# ProPrj_PowMr-Hybrid-Inverter_2024-11-03.net
KiCad netlist of a schematic drawn in EasyEDA Pro
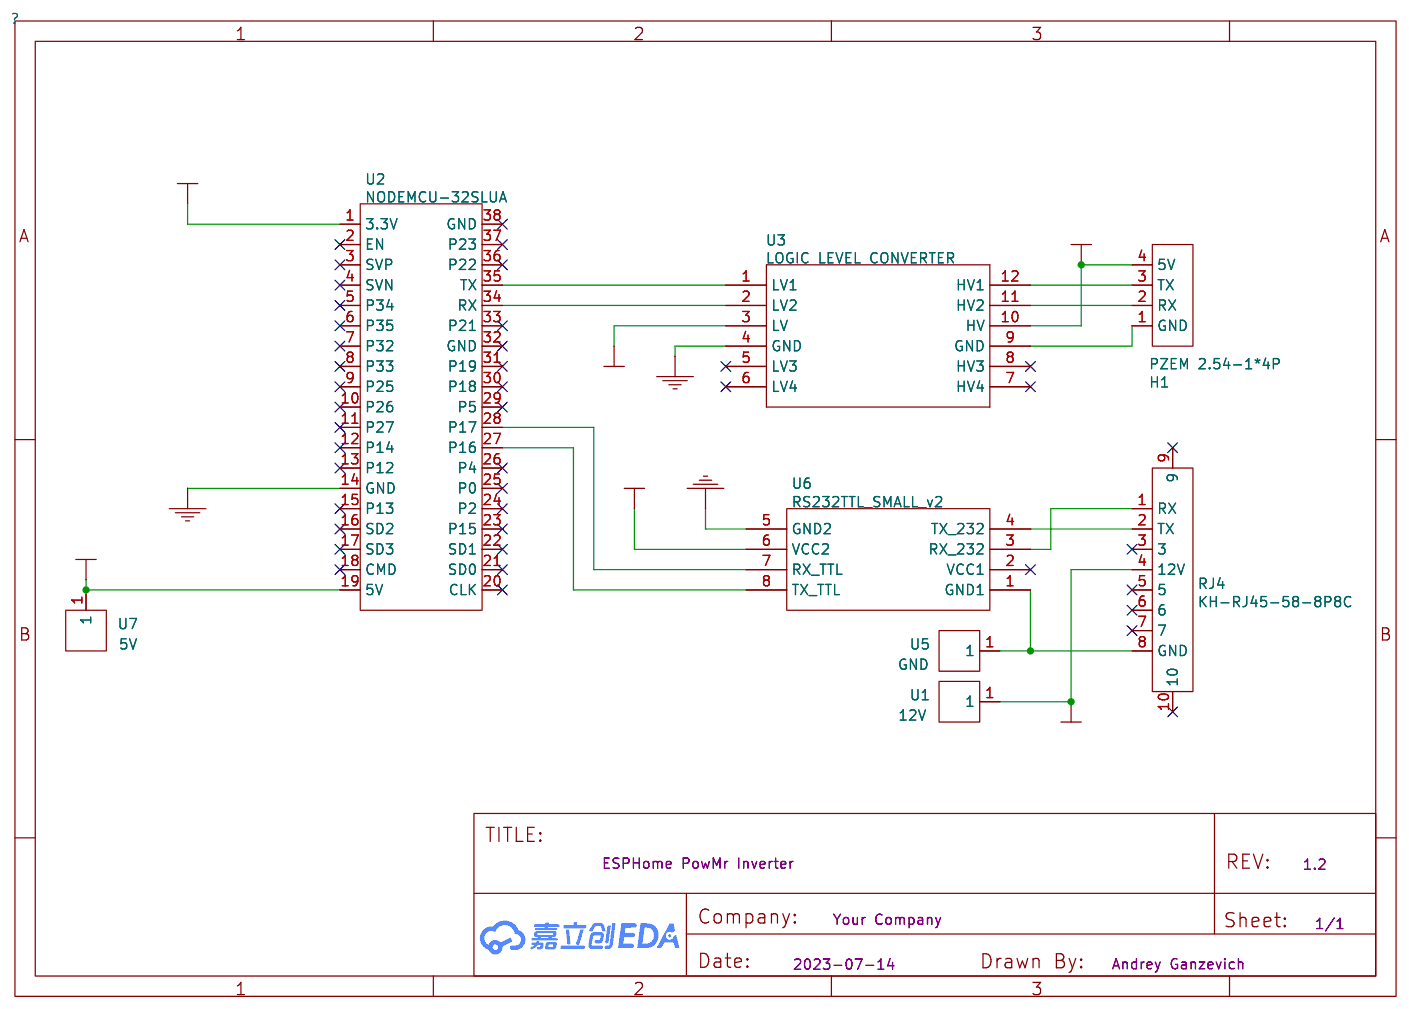
[diagram p0: Main board]
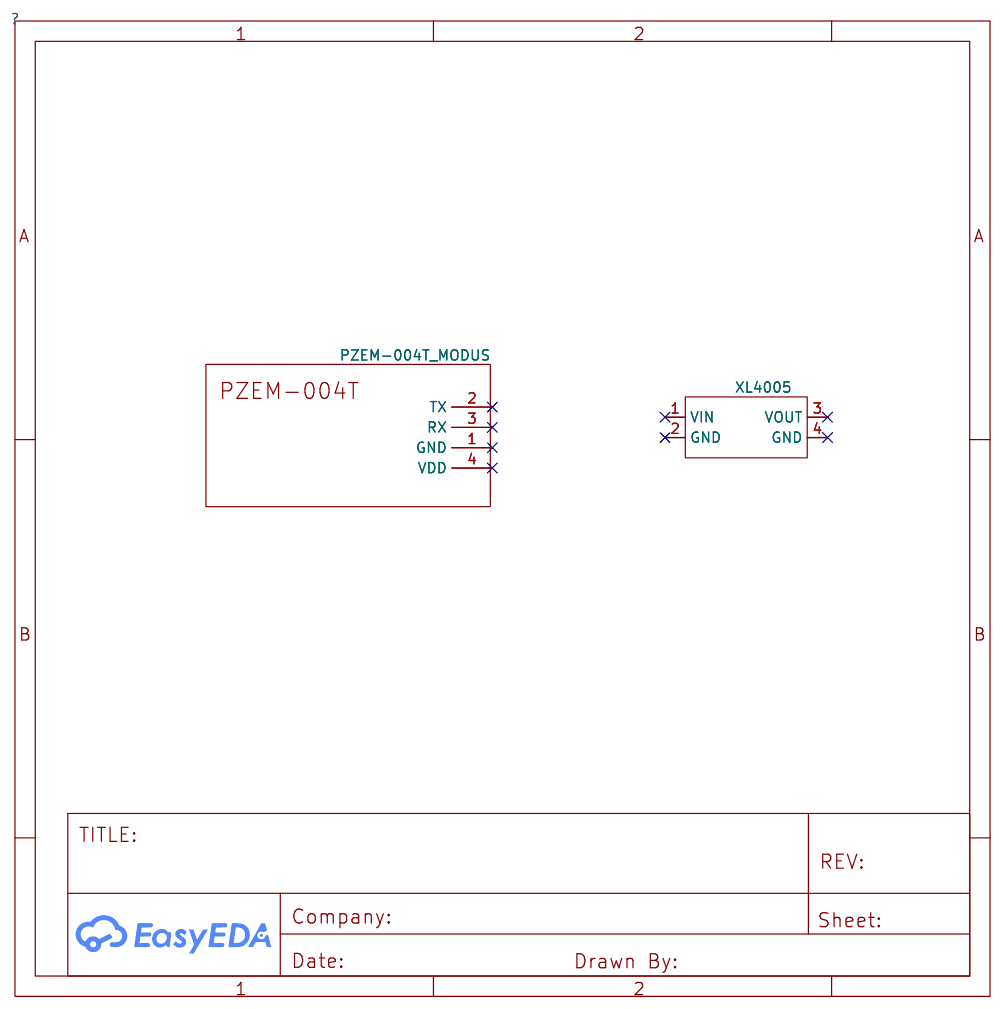
[diagram p1: Modules]

(export (version "E")
  (design (tool "Eeschema 10.0.6"))
  (components
    (comp (ref "H1")
      (value "PZEM 2.54-1*4P")
      (footprint "easyedapro:HDR-TH_4P-P2.54-H-M-W10.4")
      (fields
        (field (name "Manufacturer Part") "2.54-1*4P反弯排针")
        (field (name "Manufacturer") "BOOMELE(博穆精密)")
      )
      (libsource (lib "easyedapro") (part "PZEM 2.54-1*4P"))
    )
    (comp (ref "RJ4")
      (value "KH-RJ45-58-8P8C")
      (footprint "easyedapro:RJ45-TH_KH-RJ45-58-8P8C")
      (fields (field (name "Manufacturer") "kinghelm(金航标)"))
      (libsource (lib "easyedapro") (part "KH-RJ45-58-8P8C"))
    )
    (comp (ref "U1")
      (value "12V")
      (footprint "easyedapro:2X2MMPAD")
      (libsource (lib "easyedapro") (part "12V"))
    )
    (comp (ref "U2")
      (value "NODEMCU-32SLUA")
      (footprint "easyedapro:COMM-TH_NODEMCU-32SLUA")
      (fields
        (field (name "Manufacturer Part") "NodeMCU-32SLua")
        (field (name "Manufacturer") "Ai-Thinker(安信可)")
      )
      (libsource (lib "easyedapro") (part "NODEMCU-32SLUA"))
    )
    (comp (ref "U3")
      (value "LOGIC LEVEL CONVERTER")
      (footprint "easyedapro:LOGIC LEVEL CONVERTER")
      (libsource (lib "easyedapro") (part "LOGIC LEVEL CONVERTER"))
    )
    (comp (ref "U5")
      (value "GND")
      (footprint "easyedapro:2X2MMPAD")
      (libsource (lib "easyedapro") (part "GND"))
    )
    (comp (ref "U6")
      (value "RS232TTL_SMALL_v2")
      (footprint "easyedapro:RS232TTL_SMALL")
      (libsource (lib "easyedapro") (part "RS232TTL_SMALL_v2"))
    )
    (comp (ref "U7")
      (value "5V")
      (footprint "easyedapro:2X2MMPAD")
      (libsource (lib "easyedapro") (part "5V"))
    )
    (comp (ref "U4")
      (value "PZEM-004T_MODUS")
      (fields (field (name "Manufacturer Part") "New SchematicLib"))
      (libsource (lib "easyedapro") (part "PZEM-004T_MODUS"))
    )
    (comp (ref "U8") (value "XL4005") (libsource (lib "easyedapro") (part "XL4005")))
  )
  (nets
    (net (code "1") (name "+5V") (class "Default")
      (node (ref "H1") (pin "4") (pinfunction "5V_4") (pintype "unspecified"))
      (node (ref "U2") (pin "19") (pinfunction "5V_19") (pintype "unspecified"))
      (node (ref "U3") (pin "10") (pinfunction "HV_10") (pintype "unspecified"))
      (node (ref "U7") (pin "1") (pinfunction "1_1") (pintype "unspecified"))
    )
    (net (code "2") (name "+12V") (class "Default")
      (node (ref "RJ4") (pin "4") (pinfunction "12V_4") (pintype "unspecified"))
      (node (ref "U1") (pin "1") (pinfunction "1_1") (pintype "unspecified"))
    )
    (net (code "3") (name "GND") (class "Default")
      (node (ref "U2") (pin "14") (pinfunction "GND_14") (pintype "unspecified"))
      (node (ref "U3") (pin "4") (pinfunction "GND_4") (pintype "unspecified"))
      (node (ref "U6") (pin "5") (pinfunction "GND2_5") (pintype "unspecified"))
    )
    (net (code "4") (name "Net-(H1-GND)") (class "Default")
      (node (ref "H1") (pin "1") (pinfunction "GND_1") (pintype "unspecified"))
      (node (ref "U3") (pin "9") (pinfunction "GND_9") (pintype "unspecified"))
    )
    (net (code "5") (name "Net-(H1-RX)") (class "Default")
      (node (ref "H1") (pin "2") (pinfunction "RX_2") (pintype "unspecified"))
      (node (ref "U3") (pin "11") (pinfunction "HV2_11") (pintype "unspecified"))
    )
    (net (code "6") (name "Net-(H1-TX)") (class "Default")
      (node (ref "H1") (pin "3") (pinfunction "TX_3") (pintype "unspecified"))
      (node (ref "U3") (pin "12") (pinfunction "HV1_12") (pintype "unspecified"))
    )
    (net (code "7") (name "Net-(RJ4-GND)") (class "Default")
      (node (ref "RJ4") (pin "8") (pinfunction "GND_8") (pintype "unspecified"))
      (node (ref "U5") (pin "1") (pinfunction "1_1") (pintype "unspecified"))
      (node (ref "U6") (pin "1") (pinfunction "GND1_1") (pintype "unspecified"))
    )
    (net (code "8") (name "Net-(RJ4-RX)") (class "Default")
      (node (ref "RJ4") (pin "1") (pinfunction "RX_1") (pintype "unspecified"))
      (node (ref "U6") (pin "3") (pinfunction "RX_232_3") (pintype "unspecified"))
    )
    (net (code "9") (name "Net-(RJ4-TX)") (class "Default")
      (node (ref "RJ4") (pin "2") (pinfunction "TX_2") (pintype "unspecified"))
      (node (ref "U6") (pin "4") (pinfunction "TX_232_4") (pintype "unspecified"))
    )
    (net (code "10") (name "Net-(U2-P16)") (class "Default")
      (node (ref "U2") (pin "27") (pinfunction "P16_27") (pintype "unspecified"))
      (node (ref "U6") (pin "8") (pinfunction "TX_TTL_8") (pintype "unspecified"))
    )
    (net (code "11") (name "Net-(U2-P17)") (class "Default")
      (node (ref "U2") (pin "28") (pinfunction "P17_28") (pintype "unspecified"))
      (node (ref "U6") (pin "7") (pinfunction "RX_TTL_7") (pintype "unspecified"))
    )
    (net (code "12") (name "Net-(U2-RX)") (class "Default")
      (node (ref "U2") (pin "34") (pinfunction "RX_34") (pintype "unspecified"))
      (node (ref "U3") (pin "2") (pinfunction "LV2_2") (pintype "unspecified"))
    )
    (net (code "13") (name "Net-(U2-TX)") (class "Default")
      (node (ref "U2") (pin "35") (pinfunction "TX_35") (pintype "unspecified"))
      (node (ref "U3") (pin "1") (pinfunction "LV1_1") (pintype "unspecified"))
    )
    (net (code "14") (name "VCC") (class "Default")
      (node (ref "U2") (pin "1") (pinfunction "3.3V_1") (pintype "unspecified"))
      (node (ref "U3") (pin "3") (pinfunction "LV_3") (pintype "unspecified"))
      (node (ref "U6") (pin "6") (pinfunction "VCC2_6") (pintype "unspecified"))
    )
    (net (code "15") (name "unconnected-(RJ4-Pad3)") (class "Default")
      (node (ref "RJ4") (pin "3") (pinfunction "3_3") (pintype "unspecified+no_connect"))
    )
    (net (code "16") (name "unconnected-(RJ4-Pad5)") (class "Default")
      (node (ref "RJ4") (pin "5") (pinfunction "5_5") (pintype "unspecified+no_connect"))
    )
    (net (code "17") (name "unconnected-(RJ4-Pad6)") (class "Default")
      (node (ref "RJ4") (pin "6") (pinfunction "6_6") (pintype "unspecified+no_connect"))
    )
    (net (code "18") (name "unconnected-(RJ4-Pad7)") (class "Default")
      (node (ref "RJ4") (pin "7") (pinfunction "7_7") (pintype "unspecified+no_connect"))
    )
    (net (code "19") (name "unconnected-(RJ4-Pad9)") (class "Default")
      (node (ref "RJ4") (pin "9") (pinfunction "9_9") (pintype "unspecified+no_connect"))
    )
    (net (code "20") (name "unconnected-(RJ4-Pad10)") (class "Default")
      (node (ref "RJ4") (pin "10") (pinfunction "10_10") (pintype "unspecified+no_connect"))
    )
    (net (code "21") (name "unconnected-(U2-CLK-Pad20)") (class "Default")
      (node (ref "U2") (pin "20") (pinfunction "CLK_20") (pintype "unspecified+no_connect"))
    )
    (net (code "22") (name "unconnected-(U2-CMD-Pad18)") (class "Default")
      (node (ref "U2") (pin "18") (pinfunction "CMD_18") (pintype "unspecified+no_connect"))
    )
    (net (code "23") (name "unconnected-(U2-EN-Pad2)") (class "Default")
      (node (ref "U2") (pin "2") (pinfunction "EN_2") (pintype "unspecified+no_connect"))
    )
    (net (code "24") (name "unconnected-(U2-GND-Pad32)") (class "Default")
      (node (ref "U2") (pin "32") (pinfunction "GND_32") (pintype "unspecified+no_connect"))
    )
    (net (code "25") (name "unconnected-(U2-GND-Pad38)") (class "Default")
      (node (ref "U2") (pin "38") (pinfunction "GND_38") (pintype "unspecified+no_connect"))
    )
    (net (code "26") (name "unconnected-(U2-P0-Pad25)") (class "Default")
      (node (ref "U2") (pin "25") (pinfunction "P0_25") (pintype "unspecified+no_connect"))
    )
    (net (code "27") (name "unconnected-(U2-P2-Pad24)") (class "Default")
      (node (ref "U2") (pin "24") (pinfunction "P2_24") (pintype "unspecified+no_connect"))
    )
    (net (code "28") (name "unconnected-(U2-P4-Pad26)") (class "Default")
      (node (ref "U2") (pin "26") (pinfunction "P4_26") (pintype "unspecified+no_connect"))
    )
    (net (code "29") (name "unconnected-(U2-P5-Pad29)") (class "Default")
      (node (ref "U2") (pin "29") (pinfunction "P5_29") (pintype "unspecified+no_connect"))
    )
    (net (code "30") (name "unconnected-(U2-P12-Pad13)") (class "Default")
      (node (ref "U2") (pin "13") (pinfunction "P12_13") (pintype "unspecified+no_connect"))
    )
    (net (code "31") (name "unconnected-(U2-P13-Pad15)") (class "Default")
      (node (ref "U2") (pin "15") (pinfunction "P13_15") (pintype "unspecified+no_connect"))
    )
    (net (code "32") (name "unconnected-(U2-P14-Pad12)") (class "Default")
      (node (ref "U2") (pin "12") (pinfunction "P14_12") (pintype "unspecified+no_connect"))
    )
    (net (code "33") (name "unconnected-(U2-P15-Pad23)") (class "Default")
      (node (ref "U2") (pin "23") (pinfunction "P15_23") (pintype "unspecified+no_connect"))
    )
    (net (code "34") (name "unconnected-(U2-P18-Pad30)") (class "Default")
      (node (ref "U2") (pin "30") (pinfunction "P18_30") (pintype "unspecified+no_connect"))
    )
    (net (code "35") (name "unconnected-(U2-P19-Pad31)") (class "Default")
      (node (ref "U2") (pin "31") (pinfunction "P19_31") (pintype "unspecified+no_connect"))
    )
    (net (code "36") (name "unconnected-(U2-P21-Pad33)") (class "Default")
      (node (ref "U2") (pin "33") (pinfunction "P21_33") (pintype "unspecified+no_connect"))
    )
    (net (code "37") (name "unconnected-(U2-P22-Pad36)") (class "Default")
      (node (ref "U2") (pin "36") (pinfunction "P22_36") (pintype "unspecified+no_connect"))
    )
    (net (code "38") (name "unconnected-(U2-P23-Pad37)") (class "Default")
      (node (ref "U2") (pin "37") (pinfunction "P23_37") (pintype "unspecified+no_connect"))
    )
    (net (code "39") (name "unconnected-(U2-P25-Pad9)") (class "Default")
      (node (ref "U2") (pin "9") (pinfunction "P25_9") (pintype "unspecified+no_connect"))
    )
    (net (code "40") (name "unconnected-(U2-P26-Pad10)") (class "Default")
      (node (ref "U2") (pin "10") (pinfunction "P26_10") (pintype "unspecified+no_connect"))
    )
    (net (code "41") (name "unconnected-(U2-P27-Pad11)") (class "Default")
      (node (ref "U2") (pin "11") (pinfunction "P27_11") (pintype "unspecified+no_connect"))
    )
    (net (code "42") (name "unconnected-(U2-P32-Pad7)") (class "Default")
      (node (ref "U2") (pin "7") (pinfunction "P32_7") (pintype "unspecified+no_connect"))
    )
    (net (code "43") (name "unconnected-(U2-P33-Pad8)") (class "Default")
      (node (ref "U2") (pin "8") (pinfunction "P33_8") (pintype "unspecified+no_connect"))
    )
    (net (code "44") (name "unconnected-(U2-P34-Pad5)") (class "Default")
      (node (ref "U2") (pin "5") (pinfunction "P34_5") (pintype "unspecified+no_connect"))
    )
    (net (code "45") (name "unconnected-(U2-P35-Pad6)") (class "Default")
      (node (ref "U2") (pin "6") (pinfunction "P35_6") (pintype "unspecified+no_connect"))
    )
    (net (code "46") (name "unconnected-(U2-SD0-Pad21)") (class "Default")
      (node (ref "U2") (pin "21") (pinfunction "SD0_21") (pintype "unspecified+no_connect"))
    )
    (net (code "47") (name "unconnected-(U2-SD1-Pad22)") (class "Default")
      (node (ref "U2") (pin "22") (pinfunction "SD1_22") (pintype "unspecified+no_connect"))
    )
    (net (code "48") (name "unconnected-(U2-SD2-Pad16)") (class "Default")
      (node (ref "U2") (pin "16") (pinfunction "SD2_16") (pintype "unspecified+no_connect"))
    )
    (net (code "49") (name "unconnected-(U2-SD3-Pad17)") (class "Default")
      (node (ref "U2") (pin "17") (pinfunction "SD3_17") (pintype "unspecified+no_connect"))
    )
    (net (code "50") (name "unconnected-(U2-SVN-Pad4)") (class "Default")
      (node (ref "U2") (pin "4") (pinfunction "SVN_4") (pintype "unspecified+no_connect"))
    )
    (net (code "51") (name "unconnected-(U2-SVP-Pad3)") (class "Default")
      (node (ref "U2") (pin "3") (pinfunction "SVP_3") (pintype "unspecified+no_connect"))
    )
    (net (code "52") (name "unconnected-(U3-HV3-Pad8)") (class "Default")
      (node (ref "U3") (pin "8") (pinfunction "HV3_8") (pintype "unspecified+no_connect"))
    )
    (net (code "53") (name "unconnected-(U3-HV4-Pad7)") (class "Default")
      (node (ref "U3") (pin "7") (pinfunction "HV4_7") (pintype "unspecified+no_connect"))
    )
    (net (code "54") (name "unconnected-(U3-LV3-Pad5)") (class "Default")
      (node (ref "U3") (pin "5") (pinfunction "LV3_5") (pintype "unspecified+no_connect"))
    )
    (net (code "55") (name "unconnected-(U3-LV4-Pad6)") (class "Default")
      (node (ref "U3") (pin "6") (pinfunction "LV4_6") (pintype "unspecified+no_connect"))
    )
    (net (code "56") (name "unconnected-(U4-GND-Pad1)") (class "Default")
      (node (ref "U4") (pin "1") (pinfunction "GND_1") (pintype "unspecified+no_connect"))
    )
    (net (code "57") (name "unconnected-(U4-RX-Pad3)") (class "Default")
      (node (ref "U4") (pin "3") (pinfunction "RX_3") (pintype "unspecified+no_connect"))
    )
    (net (code "58") (name "unconnected-(U4-TX-Pad2)") (class "Default")
      (node (ref "U4") (pin "2") (pinfunction "TX_2") (pintype "unspecified+no_connect"))
    )
    (net (code "59") (name "unconnected-(U4-VDD-Pad4)") (class "Default")
      (node (ref "U4") (pin "4") (pinfunction "VDD_4") (pintype "unspecified+no_connect"))
    )
    (net (code "60") (name "unconnected-(U6-VCC1-Pad2)") (class "Default")
      (node (ref "U6") (pin "2") (pinfunction "VCC1_2") (pintype "unspecified+no_connect"))
    )
    (net (code "61") (name "unconnected-(U8-GND-Pad2)") (class "Default")
      (node (ref "U8") (pin "2") (pinfunction "GND_2") (pintype "unspecified+no_connect"))
    )
    (net (code "62") (name "unconnected-(U8-GND-Pad4)") (class "Default")
      (node (ref "U8") (pin "4") (pinfunction "GND_4") (pintype "unspecified+no_connect"))
    )
    (net (code "63") (name "unconnected-(U8-VIN-Pad1)") (class "Default")
      (node (ref "U8") (pin "1") (pinfunction "VIN_1") (pintype "unspecified+no_connect"))
    )
    (net (code "64") (name "unconnected-(U8-VOUT-Pad3)") (class "Default")
      (node (ref "U8") (pin "3") (pinfunction "VOUT_3") (pintype "unspecified+no_connect"))
    )
  )
)
